# ProPrj_Glasses_v2_0_2025-07-16.net
KiCad netlist of a schematic drawn in EasyEDA Pro
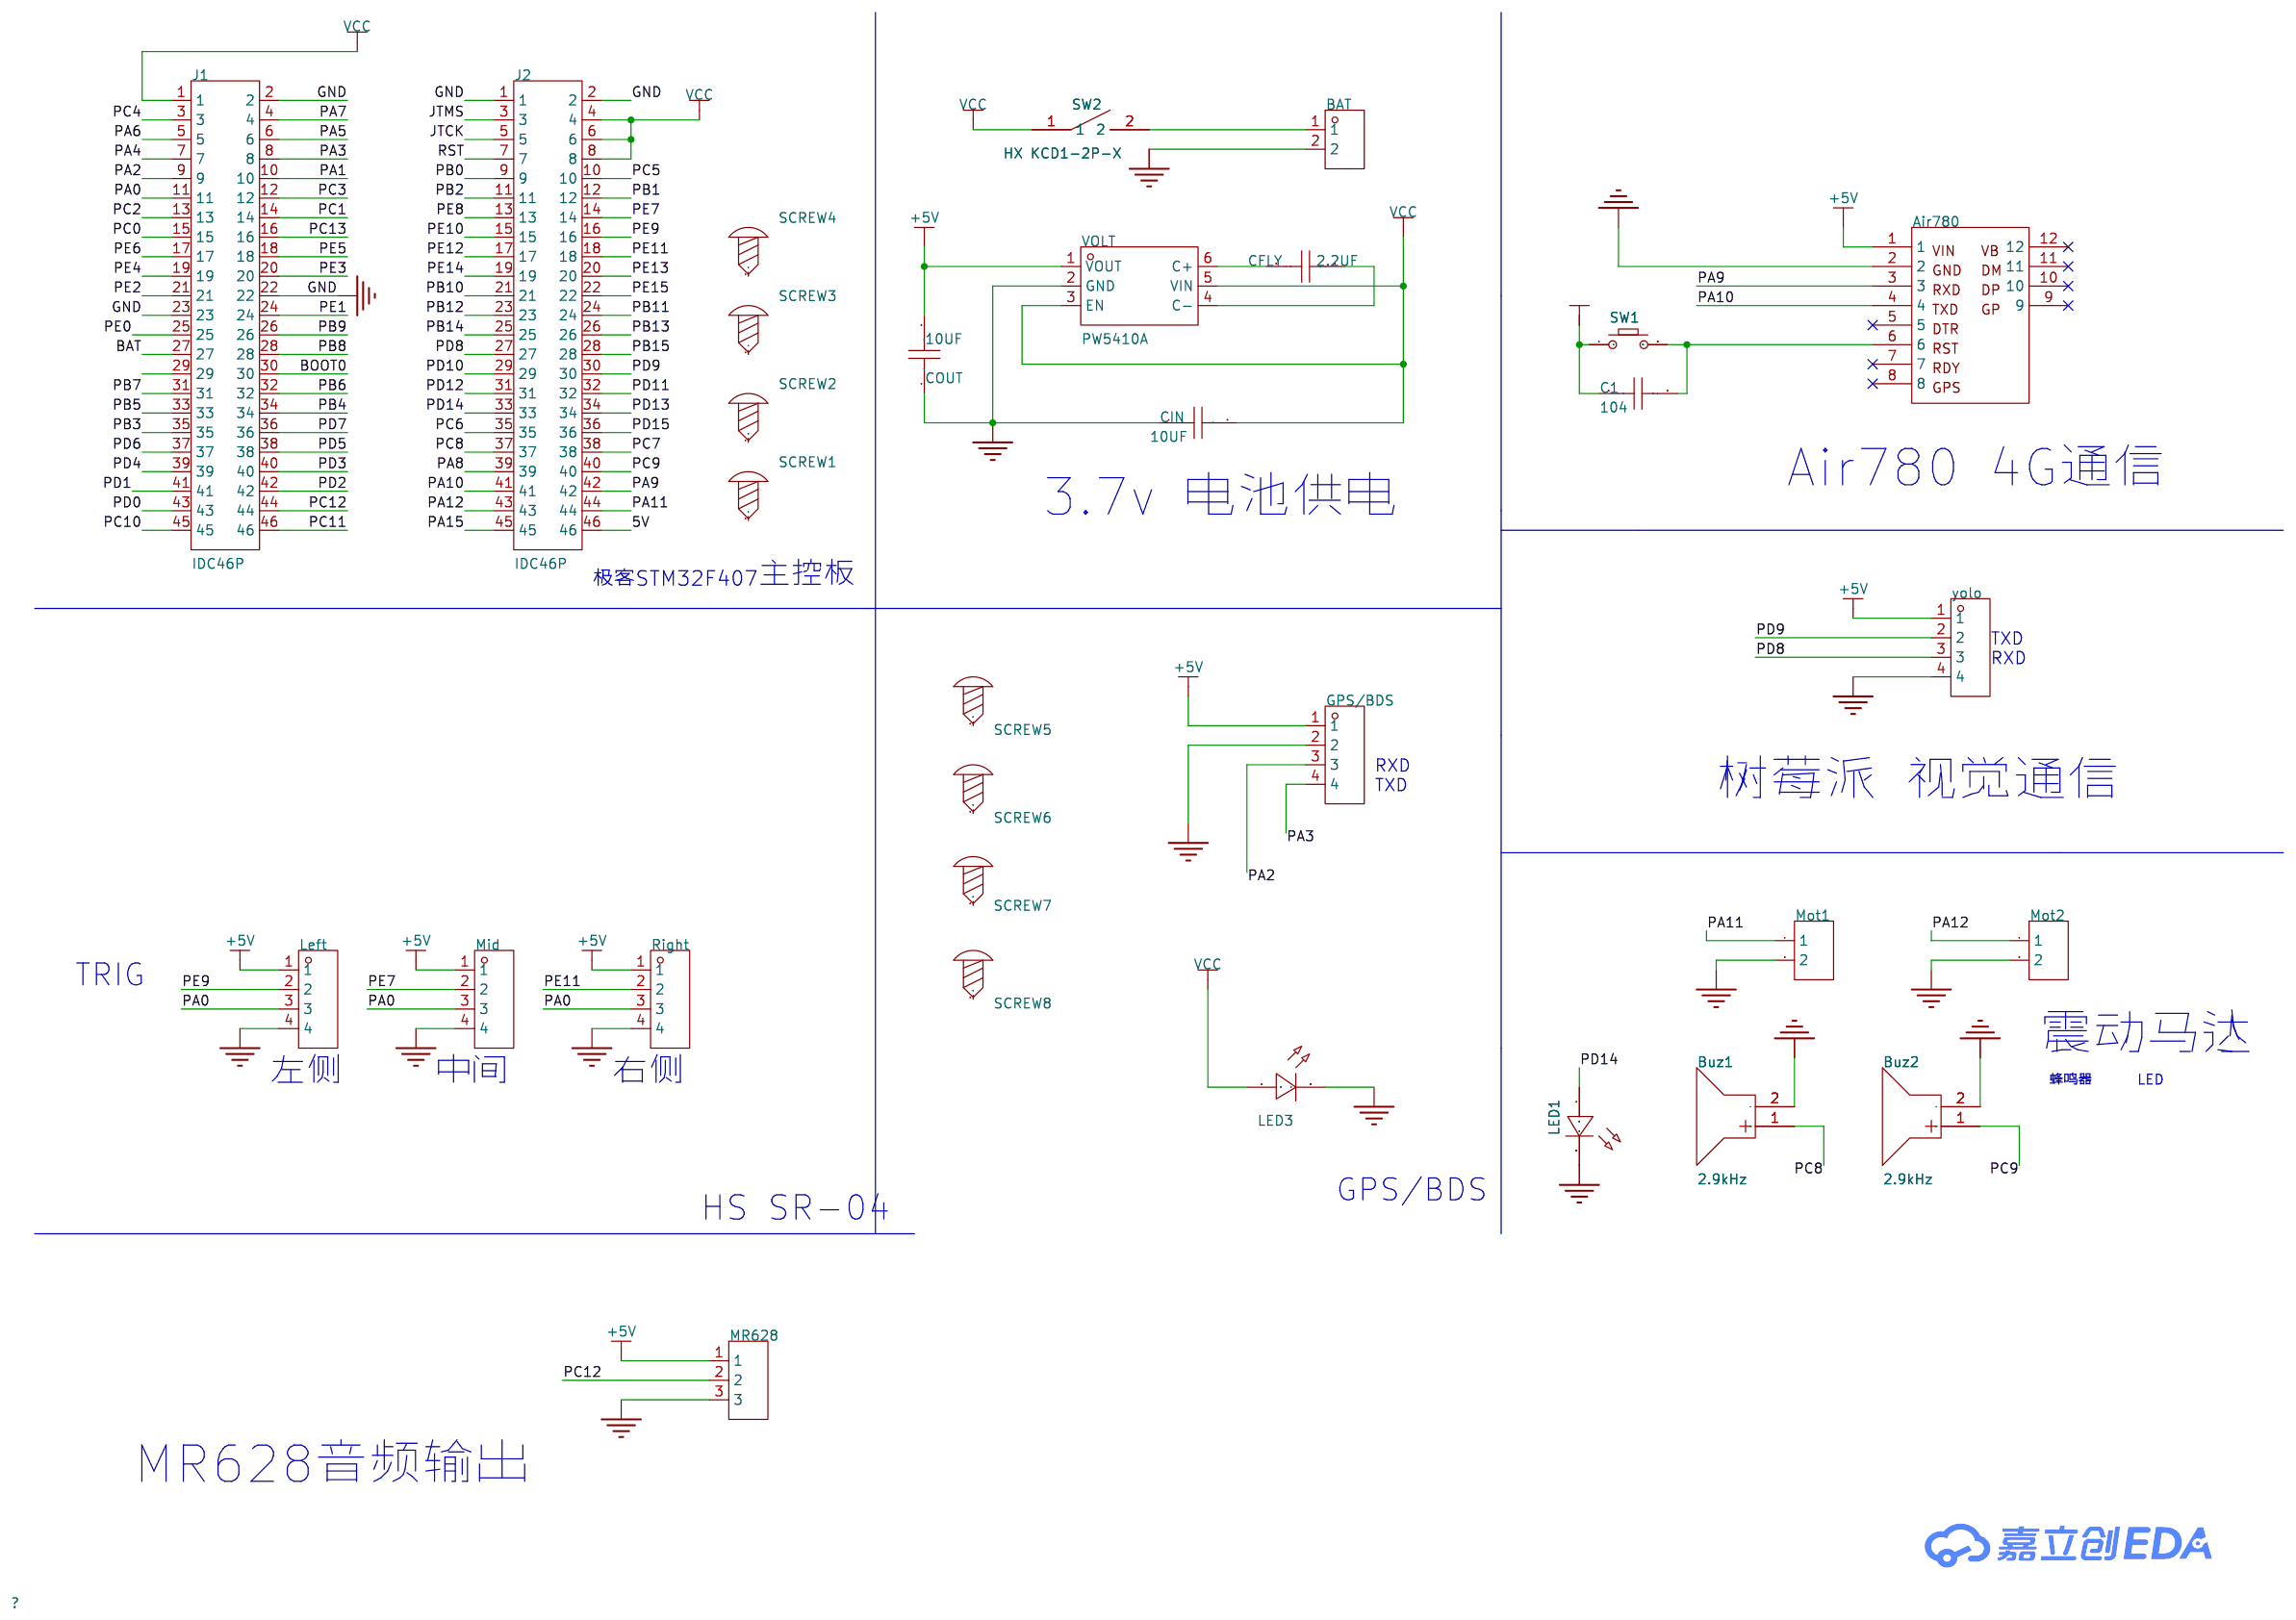
[diagram p0: schematic sheet]

(export (version "E")
  (design (tool "Eeschema 10.0.6"))
  (components
    (comp (ref "Air780")
      (value "~")
      (footprint "easyedapro:AIR780-EG")
      (libsource (lib "easyedapro") (part "AIR780"))
    )
    (comp (ref "BAT")
      (value "BAT")
      (footprint "easyedapro:CONN-TH_2P-P2.00_BOSSIE_BX-PH2.0-2PZZ")
      (libsource (lib "easyedapro") (part "PH2.0-2P_C9900095162"))
    )
    (comp (ref "Buz1")
      (value "2.9kHz")
      (footprint "easyedapro:BUZ-TH_BD9.0-P5.00-D0.6-FD")
      (description "频率:2.9kHz;声压(SPL):85dB;")
      (fields (field (name "Manufacturer Part") "HYT-0903") (field (name "Manufacturer") "HYDZ(华宇)"))
      (libsource (lib "easyedapro") (part "HYT-0903"))
    )
    (comp (ref "Buz2")
      (value "2.9kHz")
      (footprint "easyedapro:BUZ-TH_BD9.0-P5.00-D0.6-FD")
      (description "频率:2.9kHz;声压(SPL):85dB;")
      (fields (field (name "Manufacturer Part") "HYT-0903") (field (name "Manufacturer") "HYDZ(华宇)"))
      (libsource (lib "easyedapro") (part "HYT-0903"))
    )
    (comp (ref "C1")
      (value "104")
      (footprint "easyedapro:C0603")
      (libsource (lib "easyedapro") (part "CapAcitance"))
    )
    (comp (ref "CFLY")
      (value "2.2UF")
      (footprint "easyedapro:C0603")
      (libsource (lib "easyedapro") (part "CapAcitance"))
    )
    (comp (ref "CIN")
      (value "10UF")
      (footprint "easyedapro:C0603")
      (libsource (lib "easyedapro") (part "CapAcitance"))
    )
    (comp (ref "COUT")
      (value "10UF")
      (footprint "easyedapro:C0603")
      (libsource (lib "easyedapro") (part "CapAcitance"))
    )
    (comp (ref "GPS/BDS")
      (value "~")
      (footprint "easyedapro:HDR-TH_4P-P2.54-V-F")
      (libsource (lib "easyedapro") (part "2.54-1*4P母"))
    )
    (comp (ref "J1")
      (value "IDC46P")
      (footprint "easyedapro:IDC46P2.54")
      (libsource (lib "easyedapro") (part "IDC46P"))
    )
    (comp (ref "J2")
      (value "IDC46P")
      (footprint "easyedapro:IDC46P2.54")
      (libsource (lib "easyedapro") (part "IDC46P"))
    )
    (comp (ref "LED1")
      (value "~")
      (footprint "easyedapro:LED_TH-3mm")
      (libsource (lib "easyedapro") (part "LED_TH-R"))
    )
    (comp (ref "LED3")
      (value "~")
      (footprint "easyedapro:LED_TH-3mm")
      (libsource (lib "easyedapro") (part "LED_TH-G"))
    )
    (comp (ref "Left")
      (value "~")
      (footprint "easyedapro:HDR-TH_4P-P2.54-V-F")
      (libsource (lib "easyedapro") (part "2.54-1*4P母"))
    )
    (comp (ref "Mid")
      (value "~")
      (footprint "easyedapro:HDR-TH_4P-P2.54-V-F")
      (libsource (lib "easyedapro") (part "2.54-1*4P母"))
    )
    (comp (ref "Mot1")
      (value "~")
      (footprint "easyedapro:HDR-TH_2P-P2.54-V-F")
      (libsource (lib "easyedapro") (part "Header-Female-2.54_1x2"))
    )
    (comp (ref "Mot2")
      (value "~")
      (footprint "easyedapro:HDR-TH_2P-P2.54-V-F")
      (libsource (lib "easyedapro") (part "Header-Female-2.54_1x2"))
    )
    (comp (ref "MR628")
      (value "~")
      (footprint "easyedapro:HDR-TH_3P-P2.54-V-F")
      (libsource (lib "easyedapro") (part "PM254V-11-03-H85"))
    )
    (comp (ref "Right")
      (value "~")
      (footprint "easyedapro:HDR-TH_4P-P2.54-V-F")
      (libsource (lib "easyedapro") (part "2.54-1*4P母"))
    )
    (comp (ref "SCREW1")
      (value "~")
      (footprint "easyedapro:M2螺丝")
      (libsource (lib "easyedapro") (part "螺丝孔"))
    )
    (comp (ref "SCREW2")
      (value "~")
      (footprint "easyedapro:M2螺丝")
      (libsource (lib "easyedapro") (part "螺丝孔"))
    )
    (comp (ref "SCREW3")
      (value "~")
      (footprint "easyedapro:M2螺丝")
      (libsource (lib "easyedapro") (part "螺丝孔"))
    )
    (comp (ref "SCREW4")
      (value "~")
      (footprint "easyedapro:M2螺丝")
      (libsource (lib "easyedapro") (part "螺丝孔"))
    )
    (comp (ref "SCREW5")
      (value "~")
      (footprint "easyedapro:M2螺丝")
      (libsource (lib "easyedapro") (part "螺丝孔"))
    )
    (comp (ref "SCREW6")
      (value "~")
      (footprint "easyedapro:M2螺丝")
      (libsource (lib "easyedapro") (part "螺丝孔"))
    )
    (comp (ref "SCREW7")
      (value "~")
      (footprint "easyedapro:M2螺丝")
      (libsource (lib "easyedapro") (part "螺丝孔"))
    )
    (comp (ref "SCREW8")
      (value "~")
      (footprint "easyedapro:M2螺丝")
      (libsource (lib "easyedapro") (part "螺丝孔"))
    )
    (comp (ref "SW1")
      (value "~")
      (footprint "easyedapro:Key_TH_3.5x6x4.3")
      (libsource (lib "easyedapro") (part "Key_TH_3.5x6x4.3"))
    )
    (comp (ref "SW2")
      (value "HX KCD1-2P-X")
      (footprint "easyedapro:SW-TH_L22.2-W15.0-P7.00_KCD1-2P-P")
      (description "带灯:无;引脚样式:焊片;额定电流:6A;额定电压(AC):250V;电路结构:单刀单掷;机械寿命:1万次;")
      (fields (field (name "Manufacturer") "hanxia(韩下)"))
      (libsource (lib "easyedapro") (part "HX KCD1-2P-X"))
    )
    (comp (ref "VOLT")
      (value "PW5410A")
      (footprint "easyedapro:SOT-23-6_L2.9-W1.6-P0.95-LS2.8-BL")
      (libsource (lib "easyedapro") (part "PW5410A"))
    )
    (comp (ref "yolo")
      (value "~")
      (footprint "easyedapro:HDR-TH_4P-P2.54-V-F")
      (libsource (lib "easyedapro") (part "2.54-1*4P母"))
    )
  )
  (nets
    (net (code "1") (name "+3.3V") (class "Default")
      (node (ref "C1") (pin "1") (pinfunction "1_1") (pintype "input"))
      (node (ref "SW1") (pin "A") (pinfunction "A_A") (pintype "input"))
    )
    (net (code "2") (name "+5V") (class "Default")
      (node (ref "Air780") (pin "1") (pinfunction "1_1") (pintype "input"))
      (node (ref "COUT") (pin "2") (pinfunction "2_2") (pintype "input"))
      (node (ref "GPS/BDS") (pin "1") (pinfunction "1_1") (pintype "unspecified"))
      (node (ref "Left") (pin "1") (pinfunction "1_1") (pintype "unspecified"))
      (node (ref "MR628") (pin "1") (pinfunction "1_1") (pintype "unspecified"))
      (node (ref "Mid") (pin "1") (pinfunction "1_1") (pintype "unspecified"))
      (node (ref "Right") (pin "1") (pinfunction "1_1") (pintype "unspecified"))
      (node (ref "VOLT") (pin "1") (pinfunction "VOUT_1") (pintype "unspecified"))
      (node (ref "yolo") (pin "1") (pinfunction "1_1") (pintype "unspecified"))
    )
    (net (code "3") (name "/5V") (class "Default")
      (node (ref "J2") (pin "46") (pinfunction "46_46") (pintype "unspecified"))
    )
    (net (code "4") (name "/BAT") (class "Default")
      (node (ref "J1") (pin "27") (pinfunction "27_27") (pintype "unspecified"))
    )
    (net (code "5") (name "/BOOT0") (class "Default")
      (node (ref "J1") (pin "30") (pinfunction "30_30") (pintype "unspecified"))
    )
    (net (code "6") (name "/JTCK") (class "Default")
      (node (ref "J2") (pin "5") (pinfunction "5_5") (pintype "unspecified"))
    )
    (net (code "7") (name "/JTMS") (class "Default")
      (node (ref "J2") (pin "3") (pinfunction "3_3") (pintype "unspecified"))
    )
    (net (code "8") (name "/PA0") (class "Default")
      (node (ref "J1") (pin "11") (pinfunction "11_11") (pintype "unspecified"))
      (node (ref "Left") (pin "3") (pinfunction "3_3") (pintype "unspecified"))
      (node (ref "Mid") (pin "3") (pinfunction "3_3") (pintype "unspecified"))
      (node (ref "Right") (pin "3") (pinfunction "3_3") (pintype "unspecified"))
    )
    (net (code "9") (name "/PA1") (class "Default")
      (node (ref "J1") (pin "10") (pinfunction "10_10") (pintype "unspecified"))
    )
    (net (code "10") (name "/PA2") (class "Default")
      (node (ref "GPS/BDS") (pin "3") (pinfunction "3_3") (pintype "unspecified"))
      (node (ref "J1") (pin "9") (pinfunction "9_9") (pintype "unspecified"))
    )
    (net (code "11") (name "/PA3") (class "Default")
      (node (ref "GPS/BDS") (pin "4") (pinfunction "4_4") (pintype "unspecified"))
      (node (ref "J1") (pin "8") (pinfunction "8_8") (pintype "unspecified"))
    )
    (net (code "12") (name "/PA4") (class "Default")
      (node (ref "J1") (pin "7") (pinfunction "7_7") (pintype "unspecified"))
    )
    (net (code "13") (name "/PA5") (class "Default")
      (node (ref "J1") (pin "6") (pinfunction "6_6") (pintype "unspecified"))
    )
    (net (code "14") (name "/PA6") (class "Default")
      (node (ref "J1") (pin "5") (pinfunction "5_5") (pintype "unspecified"))
    )
    (net (code "15") (name "/PA7") (class "Default")
      (node (ref "J1") (pin "4") (pinfunction "4_4") (pintype "unspecified"))
    )
    (net (code "16") (name "/PA8") (class "Default")
      (node (ref "J2") (pin "39") (pinfunction "39_39") (pintype "unspecified"))
    )
    (net (code "17") (name "/PA9") (class "Default")
      (node (ref "Air780") (pin "3") (pinfunction "3_3") (pintype "input"))
      (node (ref "J2") (pin "42") (pinfunction "42_42") (pintype "unspecified"))
    )
    (net (code "18") (name "/PA10") (class "Default")
      (node (ref "Air780") (pin "4") (pinfunction "4_4") (pintype "input"))
      (node (ref "J2") (pin "41") (pinfunction "41_41") (pintype "unspecified"))
    )
    (net (code "19") (name "/PA11") (class "Default")
      (node (ref "J2") (pin "44") (pinfunction "44_44") (pintype "unspecified"))
      (node (ref "Mot1") (pin "1") (pinfunction "1_1") (pintype "input"))
    )
    (net (code "20") (name "/PA12") (class "Default")
      (node (ref "J2") (pin "43") (pinfunction "43_43") (pintype "unspecified"))
      (node (ref "Mot2") (pin "1") (pinfunction "1_1") (pintype "input"))
    )
    (net (code "21") (name "/PA15") (class "Default")
      (node (ref "J2") (pin "45") (pinfunction "45_45") (pintype "unspecified"))
    )
    (net (code "22") (name "/PB0") (class "Default")
      (node (ref "J2") (pin "9") (pinfunction "9_9") (pintype "unspecified"))
    )
    (net (code "23") (name "/PB1") (class "Default")
      (node (ref "J2") (pin "12") (pinfunction "12_12") (pintype "unspecified"))
    )
    (net (code "24") (name "/PB2") (class "Default")
      (node (ref "J2") (pin "11") (pinfunction "11_11") (pintype "unspecified"))
    )
    (net (code "25") (name "/PB3") (class "Default")
      (node (ref "J1") (pin "35") (pinfunction "35_35") (pintype "unspecified"))
    )
    (net (code "26") (name "/PB4") (class "Default")
      (node (ref "J1") (pin "34") (pinfunction "34_34") (pintype "unspecified"))
    )
    (net (code "27") (name "/PB5") (class "Default")
      (node (ref "J1") (pin "33") (pinfunction "33_33") (pintype "unspecified"))
    )
    (net (code "28") (name "/PB6") (class "Default")
      (node (ref "J1") (pin "32") (pinfunction "32_32") (pintype "unspecified"))
    )
    (net (code "29") (name "/PB7") (class "Default")
      (node (ref "J1") (pin "31") (pinfunction "31_31") (pintype "unspecified"))
    )
    (net (code "30") (name "/PB8") (class "Default")
      (node (ref "J1") (pin "28") (pinfunction "28_28") (pintype "unspecified"))
    )
    (net (code "31") (name "/PB9") (class "Default")
      (node (ref "J1") (pin "26") (pinfunction "26_26") (pintype "unspecified"))
    )
    (net (code "32") (name "/PB10") (class "Default")
      (node (ref "J2") (pin "21") (pinfunction "21_21") (pintype "unspecified"))
    )
    (net (code "33") (name "/PB11") (class "Default")
      (node (ref "J2") (pin "24") (pinfunction "24_24") (pintype "unspecified"))
    )
    (net (code "34") (name "/PB12") (class "Default")
      (node (ref "J2") (pin "23") (pinfunction "23_23") (pintype "unspecified"))
    )
    (net (code "35") (name "/PB13") (class "Default")
      (node (ref "J2") (pin "26") (pinfunction "26_26") (pintype "unspecified"))
    )
    (net (code "36") (name "/PB14") (class "Default")
      (node (ref "J2") (pin "25") (pinfunction "25_25") (pintype "unspecified"))
    )
    (net (code "37") (name "/PB15") (class "Default")
      (node (ref "J2") (pin "28") (pinfunction "28_28") (pintype "unspecified"))
    )
    (net (code "38") (name "/PC0") (class "Default")
      (node (ref "J1") (pin "15") (pinfunction "15_15") (pintype "unspecified"))
    )
    (net (code "39") (name "/PC1") (class "Default")
      (node (ref "J1") (pin "14") (pinfunction "14_14") (pintype "unspecified"))
    )
    (net (code "40") (name "/PC2") (class "Default")
      (node (ref "J1") (pin "13") (pinfunction "13_13") (pintype "unspecified"))
    )
    (net (code "41") (name "/PC3") (class "Default")
      (node (ref "J1") (pin "12") (pinfunction "12_12") (pintype "unspecified"))
    )
    (net (code "42") (name "/PC4") (class "Default")
      (node (ref "J1") (pin "3") (pinfunction "3_3") (pintype "unspecified"))
    )
    (net (code "43") (name "/PC5") (class "Default")
      (node (ref "J2") (pin "10") (pinfunction "10_10") (pintype "unspecified"))
    )
    (net (code "44") (name "/PC6") (class "Default")
      (node (ref "J2") (pin "35") (pinfunction "35_35") (pintype "unspecified"))
    )
    (net (code "45") (name "/PC7") (class "Default")
      (node (ref "J2") (pin "38") (pinfunction "38_38") (pintype "unspecified"))
    )
    (net (code "46") (name "/PC8") (class "Default")
      (node (ref "Buz1") (pin "1") (pinfunction "+_1") (pintype "unspecified"))
      (node (ref "J2") (pin "37") (pinfunction "37_37") (pintype "unspecified"))
    )
    (net (code "47") (name "/PC9") (class "Default")
      (node (ref "Buz2") (pin "1") (pinfunction "+_1") (pintype "unspecified"))
      (node (ref "J2") (pin "40") (pinfunction "40_40") (pintype "unspecified"))
    )
    (net (code "48") (name "/PC10") (class "Default")
      (node (ref "J1") (pin "45") (pinfunction "45_45") (pintype "unspecified"))
    )
    (net (code "49") (name "/PC11") (class "Default")
      (node (ref "J1") (pin "46") (pinfunction "46_46") (pintype "unspecified"))
    )
    (net (code "50") (name "/PC12") (class "Default")
      (node (ref "J1") (pin "44") (pinfunction "44_44") (pintype "unspecified"))
      (node (ref "MR628") (pin "2") (pinfunction "2_2") (pintype "unspecified"))
    )
    (net (code "51") (name "/PC13") (class "Default")
      (node (ref "J1") (pin "16") (pinfunction "16_16") (pintype "unspecified"))
    )
    (net (code "52") (name "/PD0") (class "Default")
      (node (ref "J1") (pin "43") (pinfunction "43_43") (pintype "unspecified"))
    )
    (net (code "53") (name "/PD1") (class "Default")
      (node (ref "J1") (pin "41") (pinfunction "41_41") (pintype "unspecified"))
    )
    (net (code "54") (name "/PD2") (class "Default")
      (node (ref "J1") (pin "42") (pinfunction "42_42") (pintype "unspecified"))
    )
    (net (code "55") (name "/PD3") (class "Default")
      (node (ref "J1") (pin "40") (pinfunction "40_40") (pintype "unspecified"))
    )
    (net (code "56") (name "/PD4") (class "Default")
      (node (ref "J1") (pin "39") (pinfunction "39_39") (pintype "unspecified"))
    )
    (net (code "57") (name "/PD5") (class "Default")
      (node (ref "J1") (pin "38") (pinfunction "38_38") (pintype "unspecified"))
    )
    (net (code "58") (name "/PD6") (class "Default")
      (node (ref "J1") (pin "37") (pinfunction "37_37") (pintype "unspecified"))
    )
    (net (code "59") (name "/PD7") (class "Default")
      (node (ref "J1") (pin "36") (pinfunction "36_36") (pintype "unspecified"))
    )
    (net (code "60") (name "/PD8") (class "Default")
      (node (ref "J2") (pin "27") (pinfunction "27_27") (pintype "unspecified"))
      (node (ref "yolo") (pin "3") (pinfunction "3_3") (pintype "unspecified"))
    )
    (net (code "61") (name "/PD9") (class "Default")
      (node (ref "J2") (pin "30") (pinfunction "30_30") (pintype "unspecified"))
      (node (ref "yolo") (pin "2") (pinfunction "2_2") (pintype "unspecified"))
    )
    (net (code "62") (name "/PD10") (class "Default")
      (node (ref "J2") (pin "29") (pinfunction "29_29") (pintype "unspecified"))
    )
    (net (code "63") (name "/PD11") (class "Default")
      (node (ref "J2") (pin "32") (pinfunction "32_32") (pintype "unspecified"))
    )
    (net (code "64") (name "/PD12") (class "Default")
      (node (ref "J2") (pin "31") (pinfunction "31_31") (pintype "unspecified"))
    )
    (net (code "65") (name "/PD13") (class "Default")
      (node (ref "J2") (pin "34") (pinfunction "34_34") (pintype "unspecified"))
    )
    (net (code "66") (name "/PD14") (class "Default")
      (node (ref "J2") (pin "33") (pinfunction "33_33") (pintype "unspecified"))
      (node (ref "LED1") (pin "1") (pinfunction "C_1") (pintype "input"))
    )
    (net (code "67") (name "/PD15") (class "Default")
      (node (ref "J2") (pin "36") (pinfunction "36_36") (pintype "unspecified"))
    )
    (net (code "68") (name "/PE0") (class "Default")
      (node (ref "J1") (pin "25") (pinfunction "25_25") (pintype "unspecified"))
    )
    (net (code "69") (name "/PE1") (class "Default")
      (node (ref "J1") (pin "24") (pinfunction "24_24") (pintype "unspecified"))
    )
    (net (code "70") (name "/PE2") (class "Default")
      (node (ref "J1") (pin "21") (pinfunction "21_21") (pintype "unspecified"))
    )
    (net (code "71") (name "/PE3") (class "Default")
      (node (ref "J1") (pin "20") (pinfunction "20_20") (pintype "unspecified"))
    )
    (net (code "72") (name "/PE4") (class "Default")
      (node (ref "J1") (pin "19") (pinfunction "19_19") (pintype "unspecified"))
    )
    (net (code "73") (name "/PE5") (class "Default")
      (node (ref "J1") (pin "18") (pinfunction "18_18") (pintype "unspecified"))
    )
    (net (code "74") (name "/PE6") (class "Default")
      (node (ref "J1") (pin "17") (pinfunction "17_17") (pintype "unspecified"))
    )
    (net (code "75") (name "/PE7") (class "Default")
      (node (ref "J2") (pin "14") (pinfunction "14_14") (pintype "unspecified"))
      (node (ref "Mid") (pin "2") (pinfunction "2_2") (pintype "unspecified"))
    )
    (net (code "76") (name "/PE8") (class "Default")
      (node (ref "J2") (pin "13") (pinfunction "13_13") (pintype "unspecified"))
    )
    (net (code "77") (name "/PE9") (class "Default")
      (node (ref "J2") (pin "16") (pinfunction "16_16") (pintype "unspecified"))
      (node (ref "Left") (pin "2") (pinfunction "2_2") (pintype "unspecified"))
    )
    (net (code "78") (name "/PE10") (class "Default")
      (node (ref "J2") (pin "15") (pinfunction "15_15") (pintype "unspecified"))
    )
    (net (code "79") (name "/PE11") (class "Default")
      (node (ref "J2") (pin "18") (pinfunction "18_18") (pintype "unspecified"))
      (node (ref "Right") (pin "2") (pinfunction "2_2") (pintype "unspecified"))
    )
    (net (code "80") (name "/PE12") (class "Default")
      (node (ref "J2") (pin "17") (pinfunction "17_17") (pintype "unspecified"))
    )
    (net (code "81") (name "/PE13") (class "Default")
      (node (ref "J2") (pin "20") (pinfunction "20_20") (pintype "unspecified"))
    )
    (net (code "82") (name "/PE14") (class "Default")
      (node (ref "J2") (pin "19") (pinfunction "19_19") (pintype "unspecified"))
    )
    (net (code "83") (name "/PE15") (class "Default")
      (node (ref "J2") (pin "22") (pinfunction "22_22") (pintype "unspecified"))
    )
    (net (code "84") (name "/RST") (class "Default")
      (node (ref "J2") (pin "7") (pinfunction "7_7") (pintype "unspecified"))
    )
    (net (code "85") (name "GND") (class "Default")
      (node (ref "Air780") (pin "2") (pinfunction "2_2") (pintype "input"))
      (node (ref "BAT") (pin "2") (pinfunction "2_2") (pintype "unspecified"))
      (node (ref "Buz1") (pin "2") (pinfunction "-_2") (pintype "unspecified"))
      (node (ref "Buz2") (pin "2") (pinfunction "-_2") (pintype "unspecified"))
      (node (ref "CIN") (pin "1") (pinfunction "1_1") (pintype "input"))
      (node (ref "COUT") (pin "1") (pinfunction "1_1") (pintype "input"))
      (node (ref "GPS/BDS") (pin "2") (pinfunction "2_2") (pintype "unspecified"))
      (node (ref "J1") (pin "2") (pinfunction "2_2") (pintype "unspecified"))
      (node (ref "J1") (pin "22") (pinfunction "22_22") (pintype "unspecified"))
      (node (ref "J1") (pin "23") (pinfunction "23_23") (pintype "unspecified"))
      (node (ref "J2") (pin "1") (pinfunction "1_1") (pintype "unspecified"))
      (node (ref "J2") (pin "2") (pinfunction "2_2") (pintype "unspecified"))
      (node (ref "LED1") (pin "2") (pinfunction "A_2") (pintype "input"))
      (node (ref "LED3") (pin "2") (pinfunction "A_2") (pintype "input"))
      (node (ref "Left") (pin "4") (pinfunction "4_4") (pintype "unspecified"))
      (node (ref "MR628") (pin "3") (pinfunction "3_3") (pintype "unspecified"))
      (node (ref "Mid") (pin "4") (pinfunction "4_4") (pintype "unspecified"))
      (node (ref "Mot1") (pin "2") (pinfunction "2_2") (pintype "input"))
      (node (ref "Mot2") (pin "2") (pinfunction "2_2") (pintype "input"))
      (node (ref "Right") (pin "4") (pinfunction "4_4") (pintype "unspecified"))
      (node (ref "VOLT") (pin "2") (pinfunction "GND_2") (pintype "unspecified"))
      (node (ref "yolo") (pin "4") (pinfunction "4_4") (pintype "unspecified"))
    )
    (net (code "86") (name "Net-(Air780-Pad6)") (class "Default")
      (node (ref "Air780") (pin "6") (pinfunction "6_6") (pintype "input"))
      (node (ref "C1") (pin "2") (pinfunction "2_2") (pintype "input"))
      (node (ref "SW1") (pin "B") (pinfunction "B_B") (pintype "input"))
    )
    (net (code "87") (name "Net-(BAT-Pad1)") (class "Default")
      (node (ref "BAT") (pin "1") (pinfunction "1_1") (pintype "unspecified"))
      (node (ref "SW2") (pin "2") (pinfunction "2_2") (pintype "unspecified"))
    )
    (net (code "88") (name "Net-(VOLT-C+)") (class "Default")
      (node (ref "CFLY") (pin "1") (pinfunction "1_1") (pintype "input"))
      (node (ref "VOLT") (pin "6") (pinfunction "C+_6") (pintype "unspecified"))
    )
    (net (code "89") (name "Net-(VOLT-C-)") (class "Default")
      (node (ref "CFLY") (pin "2") (pinfunction "2_2") (pintype "input"))
      (node (ref "VOLT") (pin "4") (pinfunction "C-_4") (pintype "unspecified"))
    )
    (net (code "90") (name "VCC") (class "Default")
      (node (ref "CIN") (pin "2") (pinfunction "2_2") (pintype "input"))
      (node (ref "J1") (pin "1") (pinfunction "1_1") (pintype "unspecified"))
      (node (ref "J2") (pin "4") (pinfunction "4_4") (pintype "unspecified"))
      (node (ref "J2") (pin "6") (pinfunction "6_6") (pintype "unspecified"))
      (node (ref "J2") (pin "8") (pinfunction "8_8") (pintype "unspecified"))
      (node (ref "LED3") (pin "1") (pinfunction "C_1") (pintype "input"))
      (node (ref "SW2") (pin "1") (pinfunction "1_1") (pintype "unspecified"))
      (node (ref "VOLT") (pin "3") (pinfunction "EN_3") (pintype "unspecified"))
      (node (ref "VOLT") (pin "5") (pinfunction "VIN_5") (pintype "unspecified"))
    )
    (net (code "91") (name "unconnected-(Air780-Pad5)") (class "Default")
      (node (ref "Air780") (pin "5") (pinfunction "5_5") (pintype "input+no_connect"))
    )
    (net (code "92") (name "unconnected-(Air780-Pad7)") (class "Default")
      (node (ref "Air780") (pin "7") (pinfunction "7_7") (pintype "input+no_connect"))
    )
    (net (code "93") (name "unconnected-(Air780-Pad8)") (class "Default")
      (node (ref "Air780") (pin "8") (pinfunction "8_8") (pintype "input+no_connect"))
    )
    (net (code "94") (name "unconnected-(Air780-Pad9)") (class "Default")
      (node (ref "Air780") (pin "9") (pinfunction "9_9") (pintype "input+no_connect"))
    )
    (net (code "95") (name "unconnected-(Air780-Pad10)") (class "Default")
      (node (ref "Air780") (pin "10") (pinfunction "10_10") (pintype "input+no_connect"))
    )
    (net (code "96") (name "unconnected-(Air780-Pad11)") (class "Default")
      (node (ref "Air780") (pin "11") (pinfunction "11_11") (pintype "input+no_connect"))
    )
    (net (code "97") (name "unconnected-(Air780-Pad12)") (class "Default")
      (node (ref "Air780") (pin "12") (pinfunction "12_12") (pintype "input+no_connect"))
    )
    (net (code "98") (name "unconnected-(J1-Pad29)") (class "Default")
      (node (ref "J1") (pin "29") (pinfunction "29_29") (pintype "unspecified"))
    )
    (net (code "99") (name "unconnected-(SCREW1-Pad1)") (class "Default")
      (node (ref "SCREW1") (pin "1") (pinfunction "1_1") (pintype "input"))
    )
    (net (code "100") (name "unconnected-(SCREW2-Pad1)") (class "Default")
      (node (ref "SCREW2") (pin "1") (pinfunction "1_1") (pintype "input"))
    )
    (net (code "101") (name "unconnected-(SCREW3-Pad1)") (class "Default")
      (node (ref "SCREW3") (pin "1") (pinfunction "1_1") (pintype "input"))
    )
    (net (code "102") (name "unconnected-(SCREW4-Pad1)") (class "Default")
      (node (ref "SCREW4") (pin "1") (pinfunction "1_1") (pintype "input"))
    )
    (net (code "103") (name "unconnected-(SCREW5-Pad1)") (class "Default")
      (node (ref "SCREW5") (pin "1") (pinfunction "1_1") (pintype "input"))
    )
    (net (code "104") (name "unconnected-(SCREW6-Pad1)") (class "Default")
      (node (ref "SCREW6") (pin "1") (pinfunction "1_1") (pintype "input"))
    )
    (net (code "105") (name "unconnected-(SCREW7-Pad1)") (class "Default")
      (node (ref "SCREW7") (pin "1") (pinfunction "1_1") (pintype "input"))
    )
    (net (code "106") (name "unconnected-(SCREW8-Pad1)") (class "Default")
      (node (ref "SCREW8") (pin "1") (pinfunction "1_1") (pintype "input"))
    )
  )
)
